# AltStick.net
KiCad netlist of a schematic drawn in EAGLE
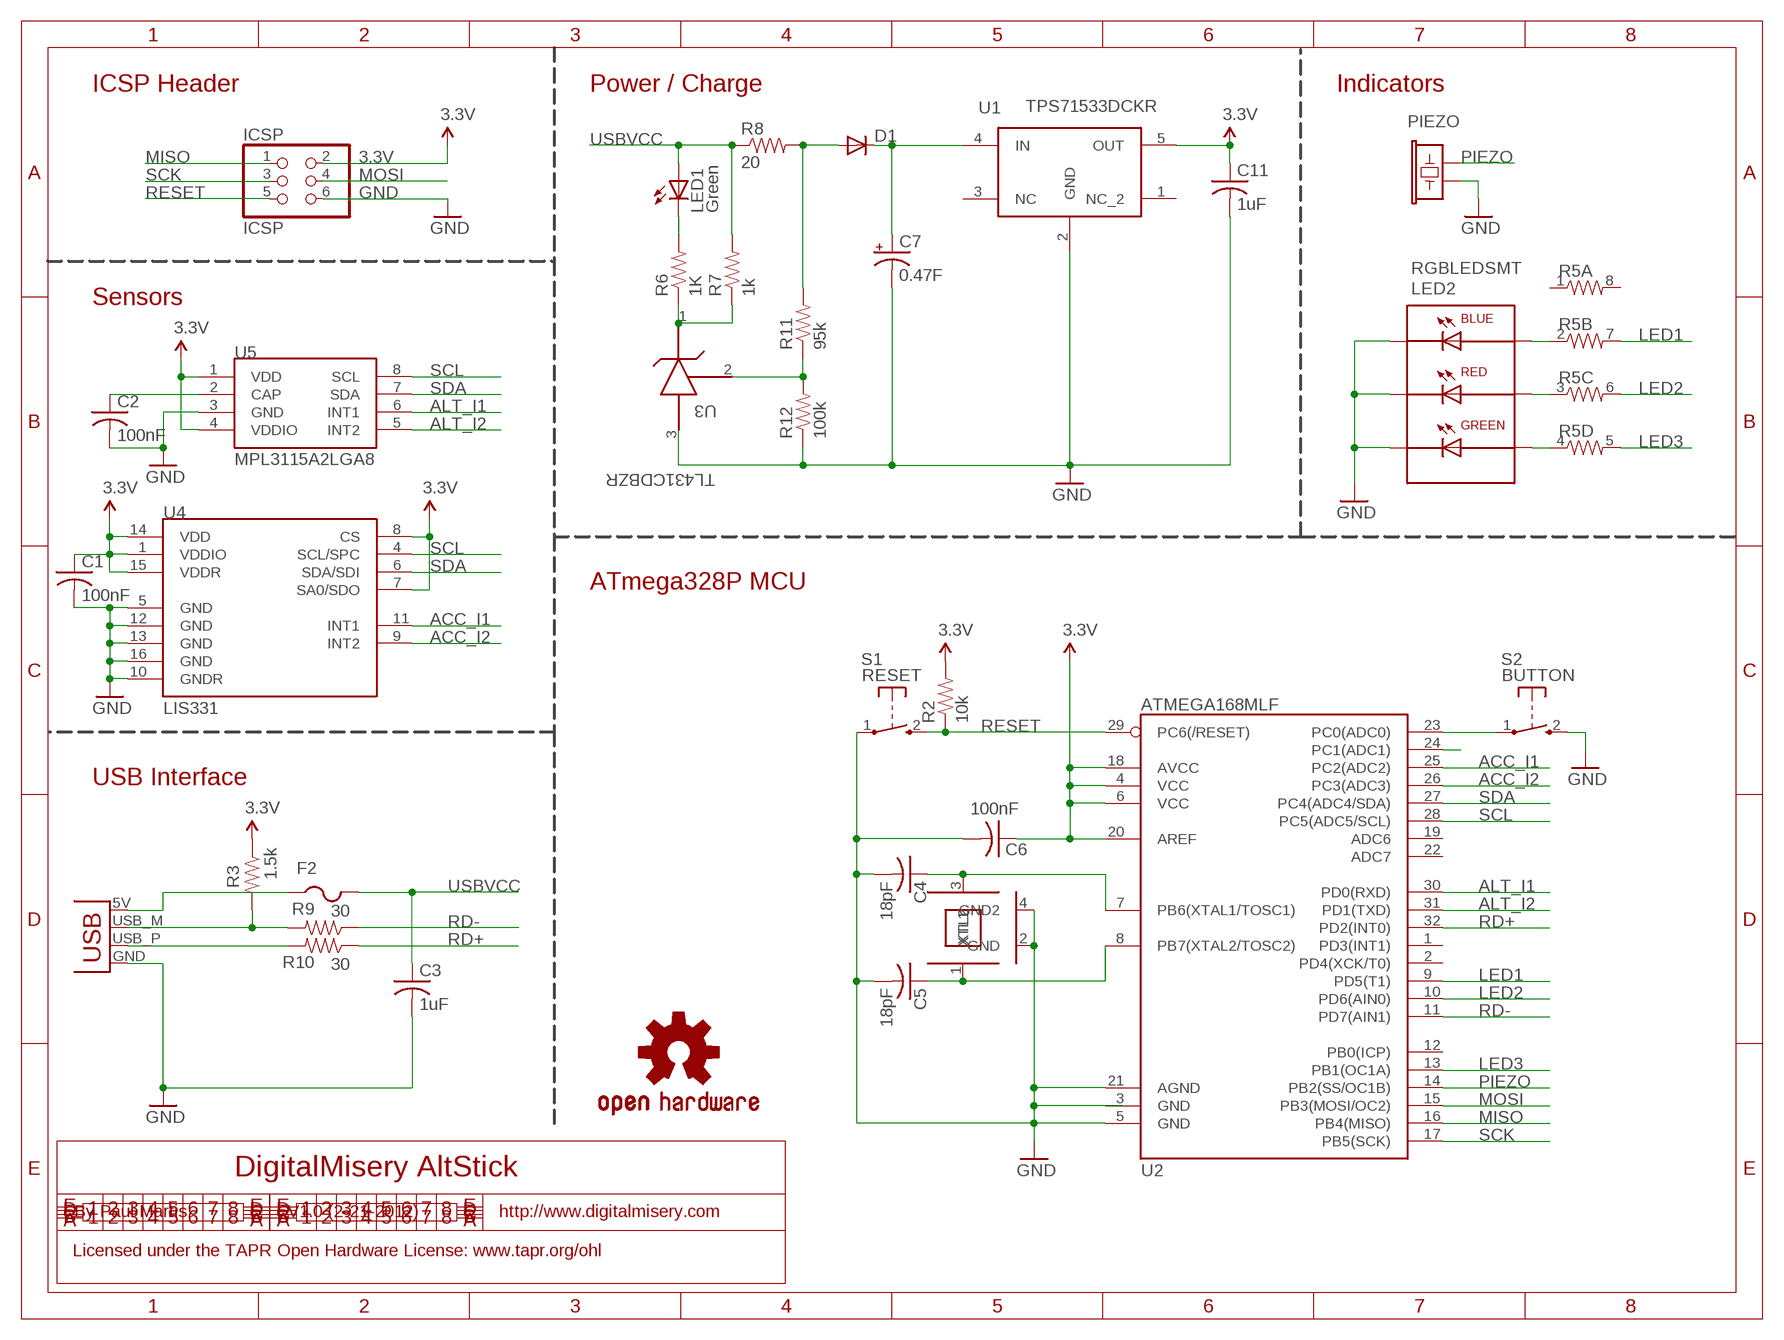
[diagram p0: schematic, sheet 1]

(export (version "E")
  (design (tool "Eeschema 10.0.6"))
  (components
    (comp (ref "C1")
      (value "100nF")
      (footprint "eagle-import:C0603")
      (libsource (lib "eagle-import") (part "C-USC0603"))
    )
    (comp (ref "C2")
      (value "100nF")
      (footprint "eagle-import:C0603")
      (libsource (lib "eagle-import") (part "C-USC0603"))
    )
    (comp (ref "C3")
      (value "1uF")
      (footprint "eagle-import:C0603")
      (libsource (lib "eagle-import") (part "C-USC0603"))
    )
    (comp (ref "C4")
      (value "18pF")
      (footprint "eagle-import:C0603")
      (libsource (lib "eagle-import") (part "C-USC0603"))
    )
    (comp (ref "C5")
      (value "18pF")
      (footprint "eagle-import:C0603")
      (libsource (lib "eagle-import") (part "C-USC0603"))
    )
    (comp (ref "C6")
      (value "100nF")
      (footprint "eagle-import:C0603")
      (libsource (lib "eagle-import") (part "C-USC0603"))
    )
    (comp (ref "C7")
      (value "0.47F")
      (footprint "eagle-import:KR-H11.5")
      (libsource (lib "eagle-import") (part "SUPERCAP"))
    )
    (comp (ref "C11")
      (value "1uF")
      (footprint "eagle-import:C0603")
      (libsource (lib "eagle-import") (part "C-USC0603"))
    )
    (comp (ref "D1")
      (value "DIODESOD")
      (footprint "eagle-import:SOD-323")
      (libsource (lib "eagle-import") (part "DIODESOD"))
    )
    (comp (ref "F2")
      (value "PTCFUSE-1206")
      (footprint "eagle-import:R1206")
      (libsource (lib "eagle-import") (part "PTCFUSE-1206"))
    )
    (comp (ref "ICSP")
      (value "ICSP")
      (footprint "eagle-import:2X03")
      (libsource (lib "eagle-import") (part "PINHD-2X3"))
    )
    (comp (ref "LED1")
      (value "Green")
      (footprint "eagle-import:LED-0603")
      (libsource (lib "eagle-import") (part "LED0603"))
    )
    (comp (ref "LED2")
      (value "RGBLEDSMT")
      (footprint "eagle-import:19-337")
      (libsource (lib "eagle-import") (part "RGBLEDSMT"))
    )
    (comp (ref "P1")
      (value "USBPCB")
      (footprint "eagle-import:USB-A-PCB")
      (libsource (lib "eagle-import") (part "USBPCB"))
    )
    (comp (ref "PIEZO")
      (value "BUZZERSMD12X12")
      (footprint "eagle-import:BUZZER-12X12-SMT")
      (libsource (lib "eagle-import") (part "BUZZERSMD12X12"))
    )
    (comp (ref "R2")
      (value "10k")
      (footprint "eagle-import:0603-RES")
      (libsource (lib "eagle-import") (part "RESISTOR0603-RES"))
    )
    (comp (ref "R3")
      (value "1.5k")
      (footprint "eagle-import:0603-RES")
      (libsource (lib "eagle-import") (part "RESISTOR0603-RES"))
    )
    (comp (ref "R5")
      (value "RESISTOR-ARRAY0603-ARV")
      (footprint "eagle-import:0603-ARV")
      (libsource (lib "eagle-import") (part "RESISTOR-ARRAY0603-ARV"))
    )
    (comp (ref "R6")
      (value "1K")
      (footprint "eagle-import:0603-RES")
      (libsource (lib "eagle-import") (part "RESISTOR0603-RES"))
    )
    (comp (ref "R7")
      (value "1k")
      (footprint "eagle-import:0603-RES")
      (libsource (lib "eagle-import") (part "RESISTOR0603-RES"))
    )
    (comp (ref "R8")
      (value "20")
      (footprint "eagle-import:0603-RES")
      (libsource (lib "eagle-import") (part "RESISTOR0603-RES"))
    )
    (comp (ref "R9")
      (value "30")
      (footprint "eagle-import:0603-RES")
      (libsource (lib "eagle-import") (part "RESISTOR0603-RES"))
    )
    (comp (ref "R10")
      (value "30")
      (footprint "eagle-import:0603-RES")
      (libsource (lib "eagle-import") (part "RESISTOR0603-RES"))
    )
    (comp (ref "R11")
      (value "95k")
      (footprint "eagle-import:0603-RES")
      (libsource (lib "eagle-import") (part "RESISTOR0603-RES"))
    )
    (comp (ref "R12")
      (value "100k")
      (footprint "eagle-import:0603-RES")
      (libsource (lib "eagle-import") (part "RESISTOR0603-RES"))
    )
    (comp (ref "S1")
      (value "RESET")
      (footprint "eagle-import:TACTILE_SWITCH_SMD_2PIN_TINY")
      (libsource (lib "eagle-import") (part "TAC_SWITCH_2PIN"))
    )
    (comp (ref "S2")
      (value "BUTTON")
      (footprint "eagle-import:TACTILE_SWITCH_SMD_2PIN_TINY")
      (libsource (lib "eagle-import") (part "TAC_SWITCH_2PIN"))
    )
    (comp (ref "U$2")
      (value "OSHW-LOGOS")
      (footprint "eagle-import:OSHW-LOGO-S")
      (libsource (lib "eagle-import") (part "OSHW-LOGOS"))
    )
    (comp (ref "U1")
      (value "TPS71533DCKR")
      (footprint "eagle-import:SOT65P210X110-5N")
      (libsource (lib "eagle-import") (part "TPS71533DCKR"))
    )
    (comp (ref "U2")
      (value "ATMEGA168MLF")
      (footprint "eagle-import:MLF32")
      (libsource (lib "eagle-import") (part "ATMEGA168MLF"))
    )
    (comp (ref "U3")
      (value "TL431CDBZR")
      (footprint "eagle-import:SOT95P237X112-3N")
      (libsource (lib "eagle-import") (part "TL431CDBZR"))
    )
    (comp (ref "U4")
      (value "LIS331")
      (footprint "eagle-import:LGA16-3MM")
      (libsource (lib "eagle-import") (part "LIS331"))
    )
    (comp (ref "U5")
      (value "MPL3115A2LGA8")
      (footprint "eagle-import:LGA8")
      (libsource (lib "eagle-import") (part "MPL3115A2LGA8"))
    )
    (comp (ref "XTL1")
      (value "12MHz")
      (footprint "eagle-import:CRYSTAL-SMD-3X2")
      (libsource (lib "eagle-import") (part "CRYSTAL-GND3X2"))
    )
  )
  (nets
    (net (code "1") (name "/ACC_I1") (class "Default")
      (node (ref "U2") (pin "25") (pinfunction "PC2(ADC2)_25") (pintype "bidirectional"))
      (node (ref "U4") (pin "11") (pinfunction "INT1_11") (pintype "bidirectional"))
    )
    (net (code "2") (name "/ACC_I2") (class "Default")
      (node (ref "U2") (pin "26") (pinfunction "PC3(ADC3)_26") (pintype "bidirectional"))
      (node (ref "U4") (pin "9") (pinfunction "INT2_9") (pintype "bidirectional"))
    )
    (net (code "3") (name "/ALT_I1") (class "Default")
      (node (ref "U2") (pin "30") (pinfunction "PD0(RXD)_30") (pintype "bidirectional"))
      (node (ref "U5") (pin "6") (pinfunction "INT1_6") (pintype "bidirectional"))
    )
    (net (code "4") (name "/ALT_I2") (class "Default")
      (node (ref "U2") (pin "31") (pinfunction "PD1(TXD)_31") (pintype "bidirectional"))
      (node (ref "U5") (pin "5") (pinfunction "INT2_5") (pintype "bidirectional"))
    )
    (net (code "5") (name "/LED1") (class "Default")
      (node (ref "R5") (pin "7") (pinfunction "2_7") (pintype "passive"))
      (node (ref "U2") (pin "9") (pinfunction "PD5(T1)_9") (pintype "bidirectional"))
    )
    (net (code "6") (name "/LED2") (class "Default")
      (node (ref "R5") (pin "6") (pinfunction "2_6") (pintype "passive"))
      (node (ref "U2") (pin "10") (pinfunction "PD6(AIN0)_10") (pintype "bidirectional"))
    )
    (net (code "7") (name "/LED3") (class "Default")
      (node (ref "R5") (pin "5") (pinfunction "2_5") (pintype "passive"))
      (node (ref "U2") (pin "13") (pinfunction "PB1(OC1A)_13") (pintype "bidirectional"))
    )
    (net (code "8") (name "/MISO") (class "Default")
      (node (ref "ICSP") (pin "1") (pinfunction "1_1") (pintype "passive"))
      (node (ref "U2") (pin "16") (pinfunction "PB4(MISO)_16") (pintype "bidirectional"))
    )
    (net (code "9") (name "/MOSI") (class "Default")
      (node (ref "ICSP") (pin "4") (pinfunction "4_4") (pintype "passive"))
      (node (ref "U2") (pin "15") (pinfunction "PB3(MOSI/OC2)_15") (pintype "bidirectional"))
    )
    (net (code "10") (name "/PIEZO") (class "Default")
      (node (ref "PIEZO") (pin "2") (pinfunction "2_2") (pintype "passive"))
      (node (ref "U2") (pin "14") (pinfunction "PB2(SS/OC1B)_14") (pintype "bidirectional"))
    )
    (net (code "11") (name "/RD+") (class "Default")
      (node (ref "R10") (pin "1") (pinfunction "1_1") (pintype "passive"))
      (node (ref "U2") (pin "32") (pinfunction "PD2(INT0)_32") (pintype "bidirectional"))
    )
    (net (code "12") (name "/RD-") (class "Default")
      (node (ref "R9") (pin "1") (pinfunction "1_1") (pintype "passive"))
      (node (ref "U2") (pin "11") (pinfunction "PD7(AIN1)_11") (pintype "bidirectional"))
    )
    (net (code "13") (name "/RESET") (class "Default")
      (node (ref "ICSP") (pin "5") (pinfunction "5_5") (pintype "passive"))
      (node (ref "R2") (pin "1") (pinfunction "1_1") (pintype "passive"))
      (node (ref "S1") (pin "2") (pinfunction "S_2") (pintype "passive"))
      (node (ref "U2") (pin "29") (pinfunction "PC6(/RESET)_29") (pintype "bidirectional"))
    )
    (net (code "14") (name "/SCK") (class "Default")
      (node (ref "ICSP") (pin "3") (pinfunction "3_3") (pintype "passive"))
      (node (ref "U2") (pin "17") (pinfunction "PB5(SCK)_17") (pintype "bidirectional"))
    )
    (net (code "15") (name "/SCL") (class "Default")
      (node (ref "U2") (pin "28") (pinfunction "PC5(ADC5/SCL)_28") (pintype "bidirectional"))
      (node (ref "U4") (pin "4") (pinfunction "SCL/SPC_4") (pintype "bidirectional"))
      (node (ref "U5") (pin "8") (pinfunction "SCL_8") (pintype "bidirectional"))
    )
    (net (code "16") (name "/SDA") (class "Default")
      (node (ref "U2") (pin "27") (pinfunction "PC4(ADC4/SDA)_27") (pintype "bidirectional"))
      (node (ref "U4") (pin "6") (pinfunction "SDA/SDI_6") (pintype "bidirectional"))
      (node (ref "U5") (pin "7") (pinfunction "SDA_7") (pintype "bidirectional"))
    )
    (net (code "17") (name "/USBVCC") (class "Default")
      (node (ref "C3") (pin "1") (pinfunction "1_1") (pintype "passive"))
      (node (ref "F2") (pin "2") (pinfunction "2_2") (pintype "passive"))
      (node (ref "LED1") (pin "A") (pinfunction "A_A") (pintype "passive"))
      (node (ref "R7") (pin "2") (pinfunction "2_2") (pintype "passive"))
      (node (ref "R8") (pin "1") (pinfunction "1_1") (pintype "passive"))
    )
    (net (code "18") (name "3.3V") (class "Default")
      (node (ref "C1") (pin "1") (pinfunction "1_1") (pintype "passive"))
      (node (ref "C11") (pin "1") (pinfunction "1_1") (pintype "passive"))
      (node (ref "C6") (pin "1") (pinfunction "1_1") (pintype "passive"))
      (node (ref "ICSP") (pin "2") (pinfunction "2_2") (pintype "passive"))
      (node (ref "R2") (pin "2") (pinfunction "2_2") (pintype "passive"))
      (node (ref "R3") (pin "1") (pinfunction "1_1") (pintype "passive"))
      (node (ref "U1") (pin "5") (pinfunction "OUT_5") (pintype "output"))
      (node (ref "U2") (pin "18") (pinfunction "AVCC_18") (pintype "bidirectional"))
      (node (ref "U2") (pin "20") (pinfunction "AREF_20") (pintype "bidirectional"))
      (node (ref "U2") (pin "4") (pinfunction "VCC_4") (pintype "bidirectional"))
      (node (ref "U2") (pin "6") (pinfunction "VCC_6") (pintype "bidirectional"))
      (node (ref "U4") (pin "1") (pinfunction "VDDIO_1") (pintype "bidirectional"))
      (node (ref "U4") (pin "14") (pinfunction "VDD_14") (pintype "bidirectional"))
      (node (ref "U4") (pin "15") (pinfunction "VDDR_15") (pintype "bidirectional"))
      (node (ref "U4") (pin "7") (pinfunction "SA0/SDO_7") (pintype "bidirectional"))
      (node (ref "U4") (pin "8") (pinfunction "CS_8") (pintype "bidirectional"))
      (node (ref "U5") (pin "1") (pinfunction "VDD_1") (pintype "bidirectional"))
      (node (ref "U5") (pin "4") (pinfunction "VDDIO_4") (pintype "bidirectional"))
    )
    (net (code "19") (name "GND") (class "Default")
      (node (ref "C1") (pin "2") (pinfunction "2_2") (pintype "passive"))
      (node (ref "C11") (pin "2") (pinfunction "2_2") (pintype "passive"))
      (node (ref "C2") (pin "2") (pinfunction "2_2") (pintype "passive"))
      (node (ref "C3") (pin "2") (pinfunction "2_2") (pintype "passive"))
      (node (ref "C4") (pin "2") (pinfunction "2_2") (pintype "passive"))
      (node (ref "C5") (pin "2") (pinfunction "2_2") (pintype "passive"))
      (node (ref "C6") (pin "2") (pinfunction "2_2") (pintype "passive"))
      (node (ref "C7") (pin "2") (pinfunction "-_2") (pintype "passive"))
      (node (ref "ICSP") (pin "6") (pinfunction "6_6") (pintype "passive"))
      (node (ref "LED2") (pin "1") (pinfunction "C-B_1") (pintype "passive"))
      (node (ref "LED2") (pin "2") (pinfunction "C-R_2") (pintype "passive"))
      (node (ref "LED2") (pin "3") (pinfunction "C-G_3") (pintype "passive"))
      (node (ref "P1") (pin "GND") (pinfunction "GND_GND") (pintype "bidirectional"))
      (node (ref "PIEZO") (pin "1") (pinfunction "1_1") (pintype "passive"))
      (node (ref "R12") (pin "1") (pinfunction "1_1") (pintype "passive"))
      (node (ref "S1") (pin "1") (pinfunction "P_1") (pintype "passive"))
      (node (ref "S2") (pin "2") (pinfunction "S_2") (pintype "passive"))
      (node (ref "U1") (pin "2") (pinfunction "GND_2") (pintype "passive"))
      (node (ref "U2") (pin "21") (pinfunction "AGND_21") (pintype "bidirectional"))
      (node (ref "U2") (pin "3") (pinfunction "GND_3") (pintype "bidirectional"))
      (node (ref "U2") (pin "5") (pinfunction "GND_5") (pintype "bidirectional"))
      (node (ref "U3") (pin "3") (pinfunction "ANODE_3") (pintype "passive"))
      (node (ref "U4") (pin "10") (pinfunction "GNDR_10") (pintype "bidirectional"))
      (node (ref "U4") (pin "12") (pinfunction "GND_12") (pintype "bidirectional"))
      (node (ref "U4") (pin "13") (pinfunction "GND_13") (pintype "bidirectional"))
      (node (ref "U4") (pin "16") (pinfunction "GND_16") (pintype "bidirectional"))
      (node (ref "U4") (pin "5") (pinfunction "GND_5") (pintype "bidirectional"))
      (node (ref "U5") (pin "3") (pinfunction "GND_3") (pintype "bidirectional"))
      (node (ref "XTL1") (pin "2") (pinfunction "GND_2") (pintype "bidirectional"))
      (node (ref "XTL1") (pin "4") (pinfunction "GND2_4") (pintype "bidirectional"))
    )
    (net (code "20") (name "Net-(C7-+)") (class "Default")
      (node (ref "C7") (pin "1") (pinfunction "+_1") (pintype "passive"))
      (node (ref "D1") (pin "1") (pinfunction "C_1") (pintype "passive"))
      (node (ref "U1") (pin "4") (pinfunction "IN_4") (pintype "power_in"))
    )
    (net (code "21") (name "Net-(D1-A)") (class "Default")
      (node (ref "D1") (pin "2") (pinfunction "A_2") (pintype "passive"))
      (node (ref "R11") (pin "2") (pinfunction "2_2") (pintype "passive"))
      (node (ref "R8") (pin "2") (pinfunction "2_2") (pintype "passive"))
    )
    (net (code "22") (name "Net-(LED1-PadC)") (class "Default")
      (node (ref "LED1") (pin "C") (pinfunction "C_C") (pintype "passive"))
      (node (ref "R6") (pin "2") (pinfunction "2_2") (pintype "passive"))
    )
    (net (code "23") (name "Net-(LED2-A-B)") (class "Default")
      (node (ref "LED2") (pin "4") (pinfunction "A-B_4") (pintype "passive"))
      (node (ref "R5") (pin "2") (pinfunction "1_2") (pintype "passive"))
    )
    (net (code "24") (name "Net-(LED2-A-G)") (class "Default")
      (node (ref "LED2") (pin "6") (pinfunction "A-G_6") (pintype "passive"))
      (node (ref "R5") (pin "4") (pinfunction "1_4") (pintype "passive"))
    )
    (net (code "25") (name "Net-(LED2-A-R)") (class "Default")
      (node (ref "LED2") (pin "5") (pinfunction "A-R_5") (pintype "passive"))
      (node (ref "R5") (pin "3") (pinfunction "1_3") (pintype "passive"))
    )
    (net (code "26") (name "Net-(P1-D+)") (class "Default")
      (node (ref "P1") (pin "USB_P") (pinfunction "D+_USB_P") (pintype "bidirectional"))
      (node (ref "R10") (pin "2") (pinfunction "2_2") (pintype "passive"))
    )
    (net (code "27") (name "Net-(P1-D-)") (class "Default")
      (node (ref "P1") (pin "USB_M") (pinfunction "D-_USB_M") (pintype "bidirectional"))
      (node (ref "R3") (pin "2") (pinfunction "2_2") (pintype "passive"))
      (node (ref "R9") (pin "2") (pinfunction "2_2") (pintype "passive"))
    )
    (net (code "28") (name "Net-(P1-VBUS)") (class "Default")
      (node (ref "F2") (pin "1") (pinfunction "1_1") (pintype "passive"))
      (node (ref "P1") (pin "5V") (pinfunction "VBUS_5V") (pintype "bidirectional"))
    )
    (net (code "29") (name "Net-(S2-P)") (class "Default")
      (node (ref "S2") (pin "1") (pinfunction "P_1") (pintype "passive"))
      (node (ref "U2") (pin "23") (pinfunction "PC0(ADC0)_23") (pintype "bidirectional"))
    )
    (net (code "30") (name "Net-(U2-PB6(XTAL1{slash}TOSC1))") (class "Default")
      (node (ref "C4") (pin "1") (pinfunction "1_1") (pintype "passive"))
      (node (ref "U2") (pin "7") (pinfunction "PB6(XTAL1/TOSC1)_7") (pintype "bidirectional"))
      (node (ref "XTL1") (pin "3") (pinfunction "XTL2_3") (pintype "bidirectional"))
    )
    (net (code "31") (name "Net-(U2-PB7(XTAL2{slash}TOSC2))") (class "Default")
      (node (ref "C5") (pin "1") (pinfunction "1_1") (pintype "passive"))
      (node (ref "U2") (pin "8") (pinfunction "PB7(XTAL2/TOSC2)_8") (pintype "bidirectional"))
      (node (ref "XTL1") (pin "1") (pinfunction "XTL1_1") (pintype "bidirectional"))
    )
    (net (code "32") (name "Net-(U3-CATHODE)") (class "Default")
      (node (ref "R6") (pin "1") (pinfunction "1_1") (pintype "passive"))
      (node (ref "R7") (pin "1") (pinfunction "1_1") (pintype "passive"))
      (node (ref "U3") (pin "1") (pinfunction "CATHODE_1") (pintype "passive"))
    )
    (net (code "33") (name "Net-(U3-REF)") (class "Default")
      (node (ref "R11") (pin "1") (pinfunction "1_1") (pintype "passive"))
      (node (ref "R12") (pin "2") (pinfunction "2_2") (pintype "passive"))
      (node (ref "U3") (pin "2") (pinfunction "REF_2") (pintype "power_in"))
    )
    (net (code "34") (name "Net-(U5-CAP)") (class "Default")
      (node (ref "C2") (pin "1") (pinfunction "1_1") (pintype "passive"))
      (node (ref "U5") (pin "2") (pinfunction "CAP_2") (pintype "bidirectional"))
    )
    (net (code "35") (name "unconnected-(R5-Pad1)") (class "Default")
      (node (ref "R5") (pin "1") (pinfunction "1_1") (pintype "passive"))
    )
    (net (code "36") (name "unconnected-(R5A-2-Pad8)") (class "Default")
      (node (ref "R5") (pin "8") (pinfunction "2_8") (pintype "passive"))
    )
    (net (code "37") (name "unconnected-(U1-NC-Pad3)") (class "Default")
      (node (ref "U1") (pin "3") (pinfunction "NC_3") (pintype "no_connect"))
    )
    (net (code "38") (name "unconnected-(U1-NC_2-Pad1)") (class "Default")
      (node (ref "U1") (pin "1") (pinfunction "NC_2_1") (pintype "no_connect"))
    )
    (net (code "39") (name "unconnected-(U2-ADC6-Pad19)") (class "Default")
      (node (ref "U2") (pin "19") (pinfunction "ADC6_19") (pintype "bidirectional"))
    )
    (net (code "40") (name "unconnected-(U2-ADC7-Pad22)") (class "Default")
      (node (ref "U2") (pin "22") (pinfunction "ADC7_22") (pintype "bidirectional"))
    )
    (net (code "41") (name "unconnected-(U2-PB0(ICP)-Pad12)") (class "Default")
      (node (ref "U2") (pin "12") (pinfunction "PB0(ICP)_12") (pintype "bidirectional"))
    )
    (net (code "42") (name "unconnected-(U2-PC1(ADC1)-Pad24)") (class "Default")
      (node (ref "U2") (pin "24") (pinfunction "PC1(ADC1)_24") (pintype "bidirectional"))
    )
    (net (code "43") (name "unconnected-(U2-PD3(INT1)-Pad1)") (class "Default")
      (node (ref "U2") (pin "1") (pinfunction "PD3(INT1)_1") (pintype "bidirectional"))
    )
    (net (code "44") (name "unconnected-(U2-PD4(XCK{slash}T0)-Pad2)") (class "Default")
      (node (ref "U2") (pin "2") (pinfunction "PD4(XCK/T0)_2") (pintype "bidirectional"))
    )
  )
)
